# motor.net
KiCad netlist of a schematic drawn in EAGLE
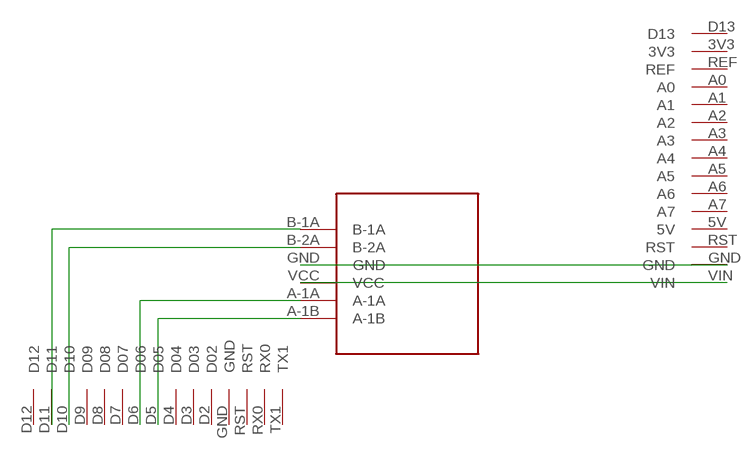
[diagram p0: schematic, sheet 1]

(export (version "E")
  (design (tool "Eeschema 10.0.6"))
  (components
    (comp (ref "U$1")
      (value "ARDUINO-NANO-JUMPER-1")
      (footprint "eagle-import:ARDUINO-NANO-JUMPER-1")
      (libsource (lib "eagle-import") (part "ARDUINO-NANO-JUMPER-1"))
    )
    (comp (ref "U$2")
      (value "L9110S")
      (footprint "eagle-import:L9100S")
      (libsource (lib "eagle-import") (part "L9110S"))
    )
    (comp (ref "U$7")
      (value "ARDUINO-NANO-JUMPER-2")
      (footprint "eagle-import:ARDUINO-NANO-JUMPER-2")
      (libsource (lib "eagle-import") (part "ARDUINO-NANO-JUMPER-2"))
    )
  )
  (nets
    (net (code "1") (name "Net-(U$1-D05)") (class "Default")
      (node (ref "U$1") (pin "D5") (pinfunction "D05_D5") (pintype "bidirectional"))
      (node (ref "U$2") (pin "A-1B") (pinfunction "A-1B_A-1B") (pintype "bidirectional"))
    )
    (net (code "2") (name "Net-(U$1-D06)") (class "Default")
      (node (ref "U$1") (pin "D6") (pinfunction "D06_D6") (pintype "bidirectional"))
      (node (ref "U$2") (pin "A-1A") (pinfunction "A-1A_A-1A") (pintype "bidirectional"))
    )
    (net (code "3") (name "Net-(U$1-PadD10)") (class "Default")
      (node (ref "U$1") (pin "D10") (pinfunction "D10_D10") (pintype "bidirectional"))
      (node (ref "U$2") (pin "B-2A") (pinfunction "B-2A_B-2A") (pintype "bidirectional"))
    )
    (net (code "4") (name "Net-(U$1-PadD11)") (class "Default")
      (node (ref "U$1") (pin "D11") (pinfunction "D11_D11") (pintype "bidirectional"))
      (node (ref "U$2") (pin "B-1A") (pinfunction "B-1A_B-1A") (pintype "bidirectional"))
    )
    (net (code "5") (name "Net-(U$2-PadGND)") (class "Default")
      (node (ref "U$2") (pin "GND") (pinfunction "GND_GND") (pintype "bidirectional"))
      (node (ref "U$7") (pin "GND") (pinfunction "GND_GND") (pintype "bidirectional"))
    )
    (net (code "6") (name "Net-(U$2-PadVCC)") (class "Default")
      (node (ref "U$2") (pin "VCC") (pinfunction "VCC_VCC") (pintype "bidirectional"))
      (node (ref "U$7") (pin "VIN") (pinfunction "VIN_VIN") (pintype "bidirectional"))
    )
    (net (code "7") (name "unconnected-(U$1-D02-PadD2)") (class "Default")
      (node (ref "U$1") (pin "D2") (pinfunction "D02_D2") (pintype "bidirectional"))
    )
    (net (code "8") (name "unconnected-(U$1-D03-PadD3)") (class "Default")
      (node (ref "U$1") (pin "D3") (pinfunction "D03_D3") (pintype "bidirectional"))
    )
    (net (code "9") (name "unconnected-(U$1-D04-PadD4)") (class "Default")
      (node (ref "U$1") (pin "D4") (pinfunction "D04_D4") (pintype "bidirectional"))
    )
    (net (code "10") (name "unconnected-(U$1-D07-PadD7)") (class "Default")
      (node (ref "U$1") (pin "D7") (pinfunction "D07_D7") (pintype "bidirectional"))
    )
    (net (code "11") (name "unconnected-(U$1-D08-PadD8)") (class "Default")
      (node (ref "U$1") (pin "D8") (pinfunction "D08_D8") (pintype "bidirectional"))
    )
    (net (code "12") (name "unconnected-(U$1-D09-PadD9)") (class "Default")
      (node (ref "U$1") (pin "D9") (pinfunction "D09_D9") (pintype "bidirectional"))
    )
    (net (code "13") (name "unconnected-(U$1-PadD12)") (class "Default")
      (node (ref "U$1") (pin "D12") (pinfunction "D12_D12") (pintype "bidirectional"))
    )
    (net (code "14") (name "unconnected-(U$1-PadGND)") (class "Default")
      (node (ref "U$1") (pin "GND") (pinfunction "GND_GND") (pintype "bidirectional"))
    )
    (net (code "15") (name "unconnected-(U$1-PadRST)") (class "Default")
      (node (ref "U$1") (pin "RST") (pinfunction "RST_RST") (pintype "bidirectional"))
    )
    (net (code "16") (name "unconnected-(U$1-PadRX0)") (class "Default")
      (node (ref "U$1") (pin "RX0") (pinfunction "RX0_RX0") (pintype "bidirectional"))
    )
    (net (code "17") (name "unconnected-(U$1-PadTX1)") (class "Default")
      (node (ref "U$1") (pin "TX1") (pinfunction "TX1_TX1") (pintype "bidirectional"))
    )
    (net (code "18") (name "unconnected-(U$7-Pad3V3)") (class "Default")
      (node (ref "U$7") (pin "3V3") (pinfunction "3V3_3V3") (pintype "bidirectional"))
    )
    (net (code "19") (name "unconnected-(U$7-Pad5V)") (class "Default")
      (node (ref "U$7") (pin "5V") (pinfunction "5V_5V") (pintype "bidirectional"))
    )
    (net (code "20") (name "unconnected-(U$7-PadA0)") (class "Default")
      (node (ref "U$7") (pin "A0") (pinfunction "A0_A0") (pintype "bidirectional"))
    )
    (net (code "21") (name "unconnected-(U$7-PadA1)") (class "Default")
      (node (ref "U$7") (pin "A1") (pinfunction "A1_A1") (pintype "bidirectional"))
    )
    (net (code "22") (name "unconnected-(U$7-PadA2)") (class "Default")
      (node (ref "U$7") (pin "A2") (pinfunction "A2_A2") (pintype "bidirectional"))
    )
    (net (code "23") (name "unconnected-(U$7-PadA3)") (class "Default")
      (node (ref "U$7") (pin "A3") (pinfunction "A3_A3") (pintype "bidirectional"))
    )
    (net (code "24") (name "unconnected-(U$7-PadA4)") (class "Default")
      (node (ref "U$7") (pin "A4") (pinfunction "A4_A4") (pintype "bidirectional"))
    )
    (net (code "25") (name "unconnected-(U$7-PadA5)") (class "Default")
      (node (ref "U$7") (pin "A5") (pinfunction "A5_A5") (pintype "bidirectional"))
    )
    (net (code "26") (name "unconnected-(U$7-PadA6)") (class "Default")
      (node (ref "U$7") (pin "A6") (pinfunction "A6_A6") (pintype "bidirectional"))
    )
    (net (code "27") (name "unconnected-(U$7-PadA7)") (class "Default")
      (node (ref "U$7") (pin "A7") (pinfunction "A7_A7") (pintype "bidirectional"))
    )
    (net (code "28") (name "unconnected-(U$7-PadD13)") (class "Default")
      (node (ref "U$7") (pin "D13") (pinfunction "D13_D13") (pintype "bidirectional"))
    )
    (net (code "29") (name "unconnected-(U$7-PadREF)") (class "Default")
      (node (ref "U$7") (pin "REF") (pinfunction "REF_REF") (pintype "bidirectional"))
    )
    (net (code "30") (name "unconnected-(U$7-PadRST)") (class "Default")
      (node (ref "U$7") (pin "RST") (pinfunction "RST_RST") (pintype "bidirectional"))
    )
  )
)
